# DM3390_CAM_FFC_MIPI_2LANE.net
KiCad netlist of a schematic drawn in Altium Designer
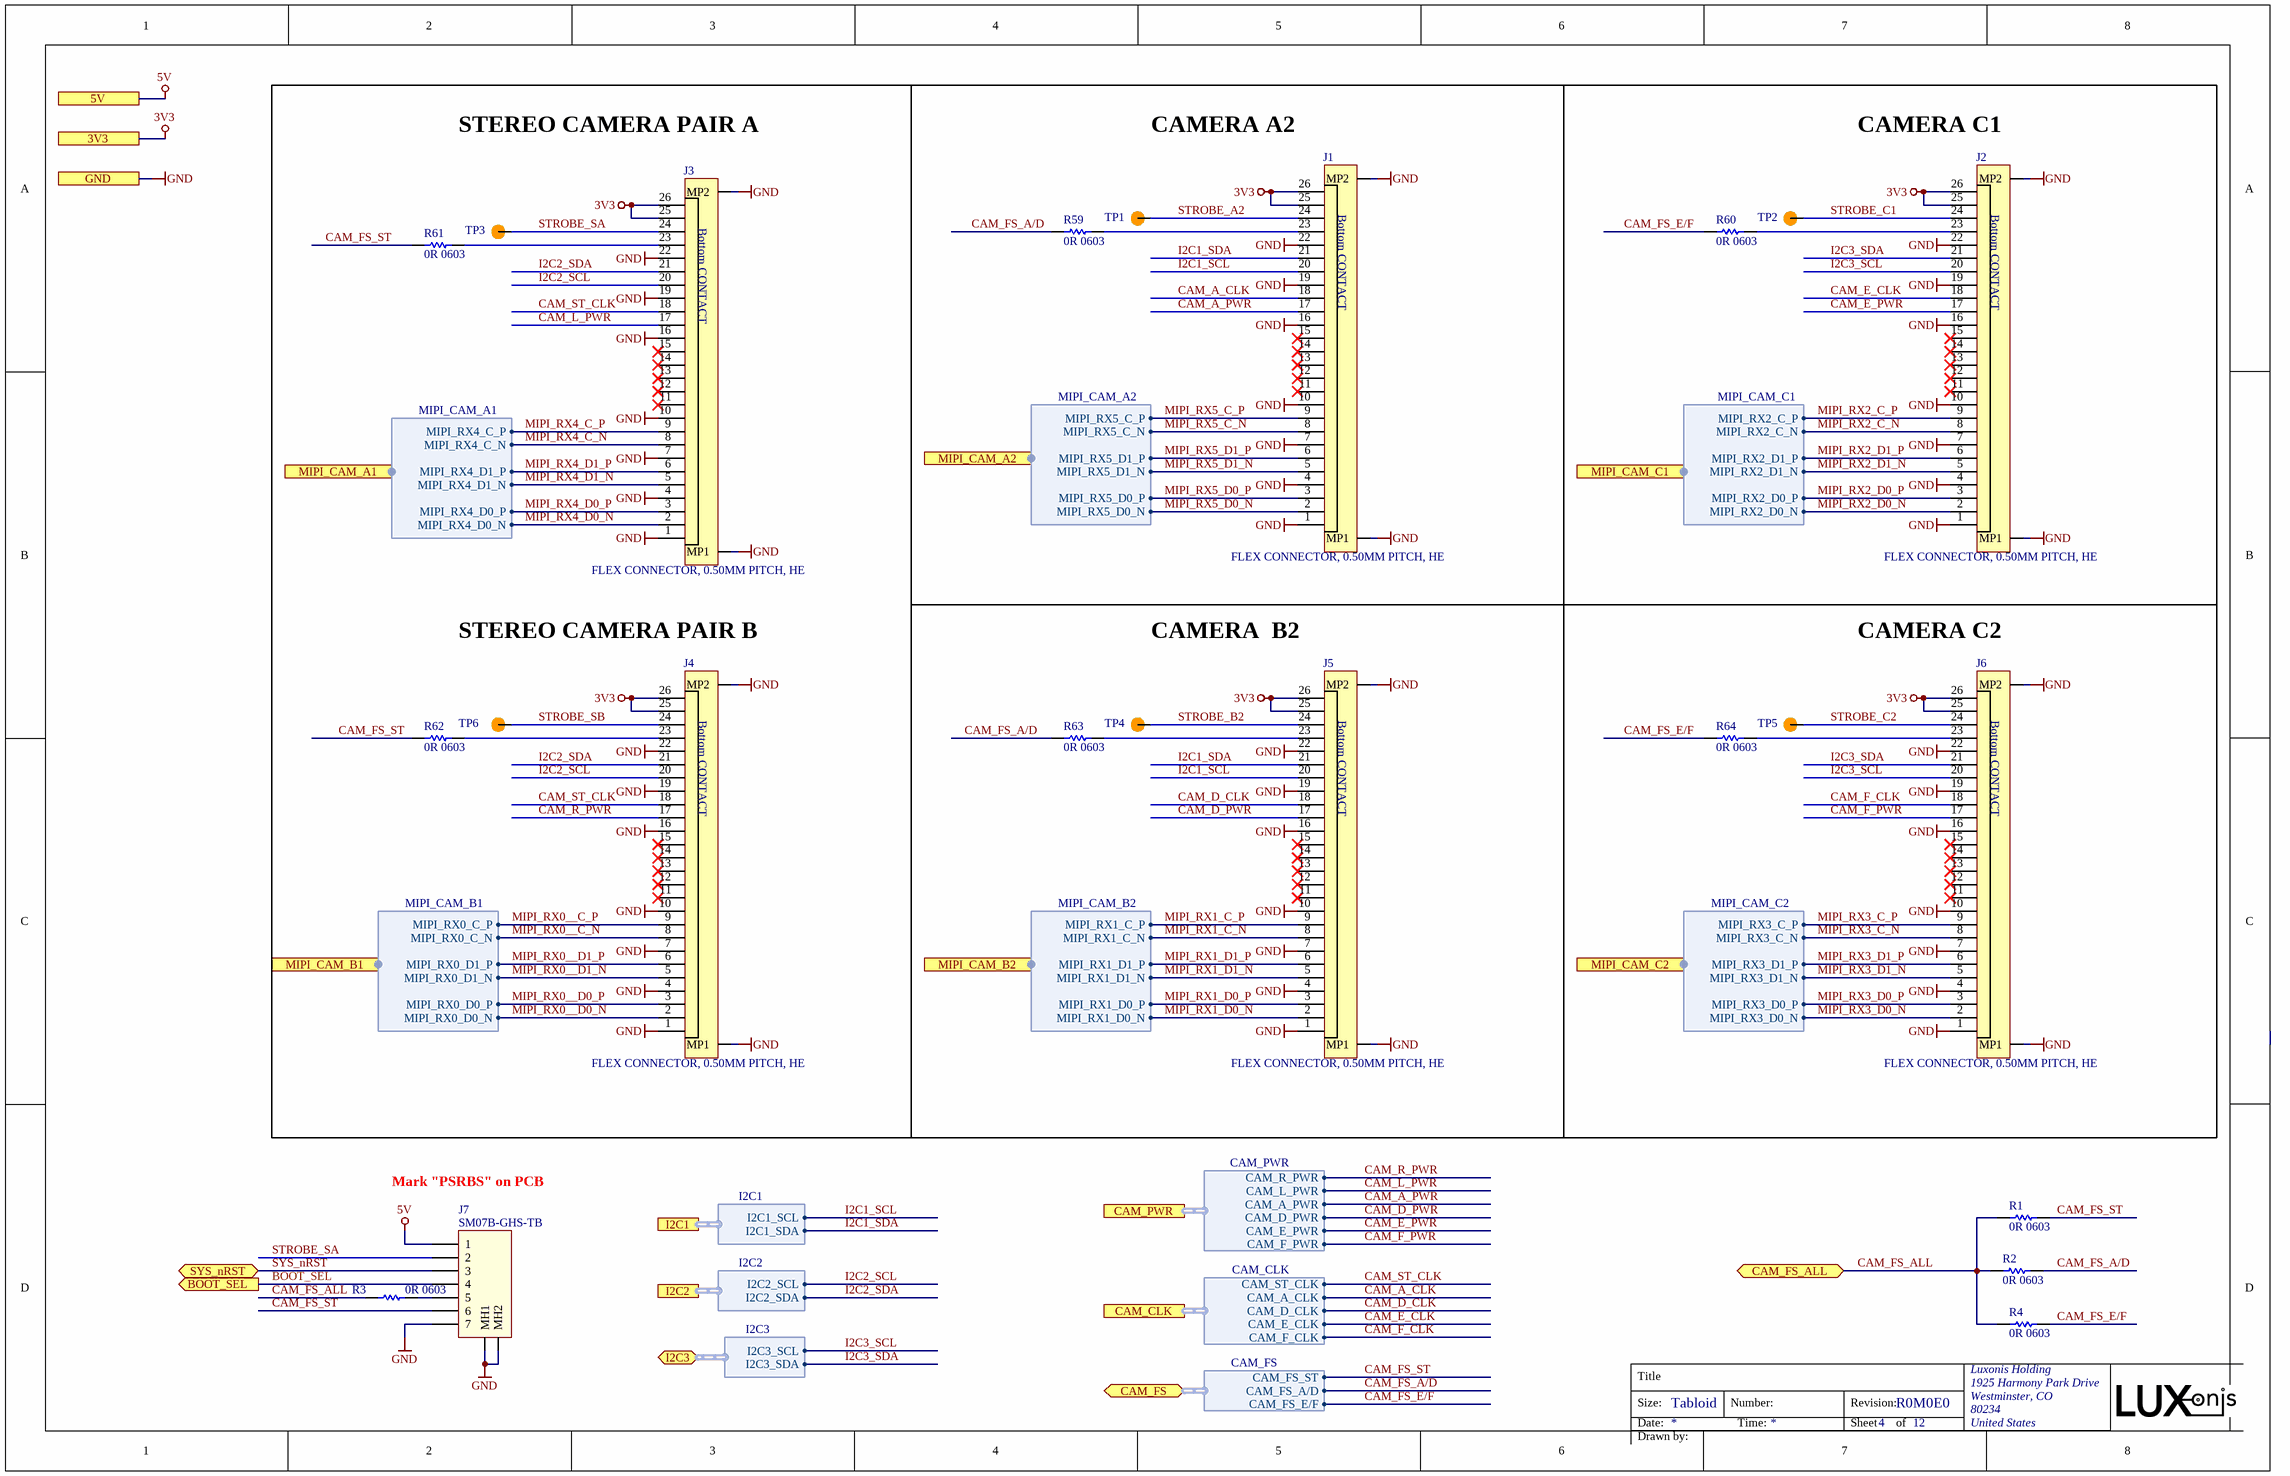
[diagram p0: DM3390_CAM_FFC_MIPI_2LANE.SchDoc]

(export (version "E")
  (design (tool "Eeschema 10.0.6"))
  (components
    (comp (ref "J1")
      (value "FLEX CONNECTOR, 0.50MM PITCH, HE")
      (footprint "F32R-1A7H1-11026")
      (description "26 Position FFC, FPC Connector Contacts, Bottom 0.020\" (0.50mm) Surface Mount, Right Angle")
      (libsource (lib "LuxonisMaster") (part "F32R-1A7H1-11026"))
    )
    (comp (ref "J2")
      (value "FLEX CONNECTOR, 0.50MM PITCH, HE")
      (footprint "F32R-1A7H1-11026")
      (description "26 Position FFC, FPC Connector Contacts, Bottom 0.020\" (0.50mm) Surface Mount, Right Angle")
      (libsource (lib "LuxonisMaster") (part "F32R-1A7H1-11026"))
    )
    (comp (ref "J3")
      (value "FLEX CONNECTOR, 0.50MM PITCH, HE")
      (footprint "F32R-1A7H1-11026")
      (description "26 Position FFC, FPC Connector Contacts, Bottom 0.020\" (0.50mm) Surface Mount, Right Angle")
      (libsource (lib "LuxonisMaster") (part "F32R-1A7H1-11026"))
    )
    (comp (ref "J4")
      (value "FLEX CONNECTOR, 0.50MM PITCH, HE")
      (footprint "F32R-1A7H1-11026")
      (description "26 Position FFC, FPC Connector Contacts, Bottom 0.020\" (0.50mm) Surface Mount, Right Angle")
      (libsource (lib "LuxonisMaster") (part "F32R-1A7H1-11026"))
    )
    (comp (ref "J5")
      (value "FLEX CONNECTOR, 0.50MM PITCH, HE")
      (footprint "F32R-1A7H1-11026")
      (description "26 Position FFC, FPC Connector Contacts, Bottom 0.020\" (0.50mm) Surface Mount, Right Angle")
      (libsource (lib "LuxonisMaster") (part "F32R-1A7H1-11026"))
    )
    (comp (ref "J6")
      (value "FLEX CONNECTOR, 0.50MM PITCH, HE")
      (footprint "F32R-1A7H1-11026")
      (description "26 Position FFC, FPC Connector Contacts, Bottom 0.020\" (0.50mm) Surface Mount, Right Angle")
      (libsource (lib "LuxonisMaster") (part "F32R-1A7H1-11026"))
    )
    (comp (ref "J7")
      (value "SM07B-GHS-TB")
      (footprint "SM07B-GHS-TB")
      (description "Conn Shrouded Header HDR 7 POS 1.25mm Solder RA Side Entry SMD T/R")
      (libsource (lib "LuxonisMaster") (part "SM07B-GHS-TB(LF)(SN)"))
    )
    (comp (ref "R1")
      (value "0R 0603")
      (footprint "RES_Altium_Vault_Generic:RESC0603(1608)_N")
      (fields (field (name "TOLERANCE") "5%"))
      (libsource (lib "LuxonisMaster") (part "CRCW06030000Z0EA"))
    )
    (comp (ref "R2")
      (value "0R 0603")
      (footprint "RES_Altium_Vault_Generic:RESC0603(1608)_N")
      (fields (field (name "TOLERANCE") "5%"))
      (libsource (lib "LuxonisMaster") (part "CRCW06030000Z0EA"))
    )
    (comp (ref "R3")
      (value "0R 0603")
      (footprint "RESC0603(1608)_N")
      (fields (field (name "TOLERANCE") "5%"))
      (libsource (lib "LuxonisMaster") (part "CRCW06030000Z0EA"))
    )
    (comp (ref "R4")
      (value "0R 0603")
      (footprint "RES_Altium_Vault_Generic:RESC0603(1608)_N")
      (fields (field (name "TOLERANCE") "5%"))
      (libsource (lib "LuxonisMaster") (part "CRCW06030000Z0EA"))
    )
    (comp (ref "R59")
      (value "0R 0603")
      (footprint "RES_Altium_Vault_Generic:RESC0603(1608)_N")
      (fields (field (name "TOLERANCE") "5%"))
      (libsource (lib "LuxonisMaster") (part "CRCW06030000Z0EA"))
    )
    (comp (ref "R60")
      (value "0R 0603")
      (footprint "RES_Altium_Vault_Generic:RESC0603(1608)_N")
      (fields (field (name "TOLERANCE") "5%"))
      (libsource (lib "LuxonisMaster") (part "CRCW06030000Z0EA"))
    )
    (comp (ref "R61")
      (value "0R 0603")
      (footprint "RES_Altium_Vault_Generic:RESC0603(1608)_N")
      (fields (field (name "TOLERANCE") "5%"))
      (libsource (lib "LuxonisMaster") (part "CRCW06030000Z0EA"))
    )
    (comp (ref "R62")
      (value "0R 0603")
      (footprint "RES_Altium_Vault_Generic:RESC0603(1608)_N")
      (fields (field (name "TOLERANCE") "5%"))
      (libsource (lib "LuxonisMaster") (part "CRCW06030000Z0EA"))
    )
    (comp (ref "R63")
      (value "0R 0603")
      (footprint "RES_Altium_Vault_Generic:RESC0603(1608)_N")
      (fields (field (name "TOLERANCE") "5%"))
      (libsource (lib "LuxonisMaster") (part "CRCW06030000Z0EA"))
    )
    (comp (ref "R64")
      (value "0R 0603")
      (footprint "RES_Altium_Vault_Generic:RESC0603(1608)_N")
      (fields (field (name "TOLERANCE") "5%"))
      (libsource (lib "LuxonisMaster") (part "CRCW06030000Z0EA"))
    )
    (comp (ref "TP1")
      (value "TP100_200_NS")
      (footprint "LuxonisMaster:TP100_200_NS")
      (libsource (lib "LuxonisMaster") (part "TEST_POINT"))
    )
    (comp (ref "TP2")
      (value "TP100_200_NS")
      (footprint "LuxonisMaster:TP100_200_NS")
      (libsource (lib "LuxonisMaster") (part "TEST_POINT"))
    )
    (comp (ref "TP3")
      (value "TP100_200_NS")
      (footprint "LuxonisMaster:TP100_200_NS")
      (libsource (lib "LuxonisMaster") (part "TEST_POINT"))
    )
    (comp (ref "TP4")
      (value "TP100_200_NS")
      (footprint "LuxonisMaster:TP100_200_NS")
      (libsource (lib "LuxonisMaster") (part "TEST_POINT"))
    )
    (comp (ref "TP5")
      (value "TP100_200_NS")
      (footprint "LuxonisMaster:TP100_200_NS")
      (libsource (lib "LuxonisMaster") (part "TEST_POINT"))
    )
    (comp (ref "TP6")
      (value "TP100_200_NS")
      (footprint "LuxonisMaster:TP100_200_NS")
      (libsource (lib "LuxonisMaster") (part "TEST_POINT"))
    )
  )
  (nets
    (net (code "13") (name "/BOOT_SEL") (class "Default")
      (node (ref "J7") (pin "4") (pinfunction "4_4") (pintype "passive"))
    )
    (net (code "14") (name "/CAM_A_CLK") (class "Default")
      (node (ref "J1") (pin "18") (pinfunction "18_18") (pintype "passive"))
    )
    (net (code "15") (name "/CAM_A_PWR") (class "Default")
      (node (ref "J1") (pin "17") (pinfunction "17_17") (pintype "passive"))
    )
    (net (code "16") (name "/CAM_D_CLK") (class "Default")
      (node (ref "J5") (pin "18") (pinfunction "18_18") (pintype "passive"))
    )
    (net (code "17") (name "/CAM_D_PWR") (class "Default")
      (node (ref "J5") (pin "17") (pinfunction "17_17") (pintype "passive"))
    )
    (net (code "18") (name "/CAM_E_CLK") (class "Default")
      (node (ref "J2") (pin "18") (pinfunction "18_18") (pintype "passive"))
    )
    (net (code "19") (name "/CAM_E_PWR") (class "Default")
      (node (ref "J2") (pin "17") (pinfunction "17_17") (pintype "passive"))
    )
    (net (code "20") (name "/CAM_FS_ALL") (class "Default")
      (node (ref "R1") (pin "1") (pinfunction "1_1") (pintype "passive"))
      (node (ref "R2") (pin "1") (pinfunction "1_1") (pintype "passive"))
      (node (ref "R3") (pin "1") (pinfunction "1_1") (pintype "passive"))
      (node (ref "R4") (pin "1") (pinfunction "1_1") (pintype "passive"))
    )
    (net (code "21") (name "/CAM_FS_A{slash}D") (class "Default")
      (node (ref "R2") (pin "2") (pinfunction "2_2") (pintype "passive"))
      (node (ref "R59") (pin "1") (pinfunction "1_1") (pintype "passive"))
      (node (ref "R63") (pin "1") (pinfunction "1_1") (pintype "passive"))
    )
    (net (code "22") (name "/CAM_FS_E{slash}F") (class "Default")
      (node (ref "R4") (pin "2") (pinfunction "2_2") (pintype "passive"))
      (node (ref "R60") (pin "1") (pinfunction "1_1") (pintype "passive"))
      (node (ref "R64") (pin "1") (pinfunction "1_1") (pintype "passive"))
    )
    (net (code "23") (name "/CAM_FS_ST") (class "Default")
      (node (ref "J7") (pin "6") (pinfunction "6_6") (pintype "passive"))
      (node (ref "R1") (pin "2") (pinfunction "2_2") (pintype "passive"))
      (node (ref "R61") (pin "1") (pinfunction "1_1") (pintype "passive"))
      (node (ref "R62") (pin "1") (pinfunction "1_1") (pintype "passive"))
    )
    (net (code "24") (name "/CAM_F_CLK") (class "Default")
      (node (ref "J6") (pin "18") (pinfunction "18_18") (pintype "passive"))
    )
    (net (code "25") (name "/CAM_F_PWR") (class "Default")
      (node (ref "J6") (pin "17") (pinfunction "17_17") (pintype "passive"))
    )
    (net (code "26") (name "/CAM_L_PWR") (class "Default")
      (node (ref "J3") (pin "17") (pinfunction "17_17") (pintype "passive"))
    )
    (net (code "27") (name "/CAM_R_PWR") (class "Default")
      (node (ref "J4") (pin "17") (pinfunction "17_17") (pintype "passive"))
    )
    (net (code "28") (name "/CAM_ST_CLK") (class "Default")
      (node (ref "J3") (pin "18") (pinfunction "18_18") (pintype "passive"))
      (node (ref "J4") (pin "18") (pinfunction "18_18") (pintype "passive"))
    )
    (net (code "29") (name "/I2C1_SCL") (class "Default")
      (node (ref "J1") (pin "20") (pinfunction "20_20") (pintype "passive"))
      (node (ref "J5") (pin "20") (pinfunction "20_20") (pintype "passive"))
    )
    (net (code "30") (name "/I2C1_SDA") (class "Default")
      (node (ref "J1") (pin "21") (pinfunction "21_21") (pintype "passive"))
      (node (ref "J5") (pin "21") (pinfunction "21_21") (pintype "passive"))
    )
    (net (code "31") (name "/I2C2_SCL") (class "Default")
      (node (ref "J3") (pin "20") (pinfunction "20_20") (pintype "passive"))
      (node (ref "J4") (pin "20") (pinfunction "20_20") (pintype "passive"))
    )
    (net (code "32") (name "/I2C2_SDA") (class "Default")
      (node (ref "J3") (pin "21") (pinfunction "21_21") (pintype "passive"))
      (node (ref "J4") (pin "21") (pinfunction "21_21") (pintype "passive"))
    )
    (net (code "33") (name "/I2C3_SCL") (class "Default")
      (node (ref "J2") (pin "20") (pinfunction "20_20") (pintype "passive"))
      (node (ref "J6") (pin "20") (pinfunction "20_20") (pintype "passive"))
    )
    (net (code "34") (name "/I2C3_SDA") (class "Default")
      (node (ref "J2") (pin "21") (pinfunction "21_21") (pintype "passive"))
      (node (ref "J6") (pin "21") (pinfunction "21_21") (pintype "passive"))
    )
    (net (code "35") (name "/MIPI_RX0__C_N") (class "Default")
      (node (ref "J4") (pin "8") (pinfunction "8_8") (pintype "passive"))
    )
    (net (code "36") (name "/MIPI_RX0__C_P") (class "Default")
      (node (ref "J4") (pin "9") (pinfunction "9_9") (pintype "passive"))
    )
    (net (code "37") (name "/MIPI_RX0__D0_N") (class "Default")
      (node (ref "J4") (pin "2") (pinfunction "2_2") (pintype "passive"))
    )
    (net (code "38") (name "/MIPI_RX0__D0_P") (class "Default")
      (node (ref "J4") (pin "3") (pinfunction "3_3") (pintype "passive"))
    )
    (net (code "39") (name "/MIPI_RX0__D1_N") (class "Default")
      (node (ref "J4") (pin "5") (pinfunction "5_5") (pintype "passive"))
    )
    (net (code "40") (name "/MIPI_RX0__D1_P") (class "Default")
      (node (ref "J4") (pin "6") (pinfunction "6_6") (pintype "passive"))
    )
    (net (code "41") (name "/MIPI_RX1_C_N") (class "Default")
      (node (ref "J5") (pin "8") (pinfunction "8_8") (pintype "passive"))
    )
    (net (code "42") (name "/MIPI_RX1_C_P") (class "Default")
      (node (ref "J5") (pin "9") (pinfunction "9_9") (pintype "passive"))
    )
    (net (code "43") (name "/MIPI_RX1_D0_N") (class "Default")
      (node (ref "J5") (pin "2") (pinfunction "2_2") (pintype "passive"))
    )
    (net (code "44") (name "/MIPI_RX1_D0_P") (class "Default")
      (node (ref "J5") (pin "3") (pinfunction "3_3") (pintype "passive"))
    )
    (net (code "45") (name "/MIPI_RX1_D1_N") (class "Default")
      (node (ref "J5") (pin "5") (pinfunction "5_5") (pintype "passive"))
    )
    (net (code "46") (name "/MIPI_RX1_D1_P") (class "Default")
      (node (ref "J5") (pin "6") (pinfunction "6_6") (pintype "passive"))
    )
    (net (code "47") (name "/MIPI_RX2_C_N") (class "Default")
      (node (ref "J2") (pin "8") (pinfunction "8_8") (pintype "passive"))
    )
    (net (code "48") (name "/MIPI_RX2_C_P") (class "Default")
      (node (ref "J2") (pin "9") (pinfunction "9_9") (pintype "passive"))
    )
    (net (code "49") (name "/MIPI_RX2_D0_N") (class "Default")
      (node (ref "J2") (pin "2") (pinfunction "2_2") (pintype "passive"))
    )
    (net (code "50") (name "/MIPI_RX2_D0_P") (class "Default")
      (node (ref "J2") (pin "3") (pinfunction "3_3") (pintype "passive"))
    )
    (net (code "51") (name "/MIPI_RX2_D1_N") (class "Default")
      (node (ref "J2") (pin "5") (pinfunction "5_5") (pintype "passive"))
    )
    (net (code "52") (name "/MIPI_RX2_D1_P") (class "Default")
      (node (ref "J2") (pin "6") (pinfunction "6_6") (pintype "passive"))
    )
    (net (code "53") (name "/MIPI_RX3_C_N") (class "Default")
      (node (ref "J6") (pin "8") (pinfunction "8_8") (pintype "passive"))
    )
    (net (code "54") (name "/MIPI_RX3_C_P") (class "Default")
      (node (ref "J6") (pin "9") (pinfunction "9_9") (pintype "passive"))
    )
    (net (code "55") (name "/MIPI_RX3_D0_N") (class "Default")
      (node (ref "J6") (pin "2") (pinfunction "2_2") (pintype "passive"))
    )
    (net (code "56") (name "/MIPI_RX3_D0_P") (class "Default")
      (node (ref "J6") (pin "3") (pinfunction "3_3") (pintype "passive"))
    )
    (net (code "57") (name "/MIPI_RX3_D1_N") (class "Default")
      (node (ref "J6") (pin "5") (pinfunction "5_5") (pintype "passive"))
    )
    (net (code "58") (name "/MIPI_RX3_D1_P") (class "Default")
      (node (ref "J6") (pin "6") (pinfunction "6_6") (pintype "passive"))
    )
    (net (code "59") (name "/MIPI_RX4_C_N") (class "Default")
      (node (ref "J3") (pin "8") (pinfunction "8_8") (pintype "passive"))
    )
    (net (code "60") (name "/MIPI_RX4_C_P") (class "Default")
      (node (ref "J3") (pin "9") (pinfunction "9_9") (pintype "passive"))
    )
    (net (code "61") (name "/MIPI_RX4_D0_N") (class "Default")
      (node (ref "J3") (pin "2") (pinfunction "2_2") (pintype "passive"))
    )
    (net (code "62") (name "/MIPI_RX4_D0_P") (class "Default")
      (node (ref "J3") (pin "3") (pinfunction "3_3") (pintype "passive"))
    )
    (net (code "63") (name "/MIPI_RX4_D1_N") (class "Default")
      (node (ref "J3") (pin "5") (pinfunction "5_5") (pintype "passive"))
    )
    (net (code "64") (name "/MIPI_RX4_D1_P") (class "Default")
      (node (ref "J3") (pin "6") (pinfunction "6_6") (pintype "passive"))
    )
    (net (code "65") (name "/MIPI_RX5_C_N") (class "Default")
      (node (ref "J1") (pin "8") (pinfunction "8_8") (pintype "passive"))
    )
    (net (code "66") (name "/MIPI_RX5_C_P") (class "Default")
      (node (ref "J1") (pin "9") (pinfunction "9_9") (pintype "passive"))
    )
    (net (code "67") (name "/MIPI_RX5_D0_N") (class "Default")
      (node (ref "J1") (pin "2") (pinfunction "2_2") (pintype "passive"))
    )
    (net (code "68") (name "/MIPI_RX5_D0_P") (class "Default")
      (node (ref "J1") (pin "3") (pinfunction "3_3") (pintype "passive"))
    )
    (net (code "69") (name "/MIPI_RX5_D1_N") (class "Default")
      (node (ref "J1") (pin "5") (pinfunction "5_5") (pintype "passive"))
    )
    (net (code "70") (name "/MIPI_RX5_D1_P") (class "Default")
      (node (ref "J1") (pin "6") (pinfunction "6_6") (pintype "passive"))
    )
    (net (code "71") (name "/STROBE_A2") (class "Default")
      (node (ref "J1") (pin "24") (pinfunction "24_24") (pintype "passive"))
      (node (ref "TP1") (pin "1") (pintype "passive"))
    )
    (net (code "72") (name "/STROBE_B2") (class "Default")
      (node (ref "J5") (pin "24") (pinfunction "24_24") (pintype "passive"))
      (node (ref "TP4") (pin "1") (pintype "passive"))
    )
    (net (code "73") (name "/STROBE_C1") (class "Default")
      (node (ref "J2") (pin "24") (pinfunction "24_24") (pintype "passive"))
      (node (ref "TP2") (pin "1") (pintype "passive"))
    )
    (net (code "74") (name "/STROBE_C2") (class "Default")
      (node (ref "J6") (pin "24") (pinfunction "24_24") (pintype "passive"))
      (node (ref "TP5") (pin "1") (pintype "passive"))
    )
    (net (code "75") (name "/STROBE_SA") (class "Default")
      (node (ref "J3") (pin "24") (pinfunction "24_24") (pintype "passive"))
      (node (ref "J7") (pin "2") (pinfunction "2_2") (pintype "passive"))
      (node (ref "TP3") (pin "1") (pintype "passive"))
    )
    (net (code "76") (name "/STROBE_SB") (class "Default")
      (node (ref "J4") (pin "24") (pinfunction "24_24") (pintype "passive"))
      (node (ref "TP6") (pin "1") (pintype "passive"))
    )
    (net (code "77") (name "/SYS_nRST") (class "Default")
      (node (ref "J7") (pin "3") (pinfunction "3_3") (pintype "passive"))
    )
    (net (code "90") (name "3V3") (class "Default")
      (node (ref "J1") (pin "25") (pinfunction "25_25") (pintype "passive"))
      (node (ref "J1") (pin "26") (pinfunction "26_26") (pintype "passive"))
      (node (ref "J2") (pin "25") (pinfunction "25_25") (pintype "passive"))
      (node (ref "J2") (pin "26") (pinfunction "26_26") (pintype "passive"))
      (node (ref "J3") (pin "25") (pinfunction "25_25") (pintype "passive"))
      (node (ref "J3") (pin "26") (pinfunction "26_26") (pintype "passive"))
      (node (ref "J4") (pin "25") (pinfunction "25_25") (pintype "passive"))
      (node (ref "J4") (pin "26") (pinfunction "26_26") (pintype "passive"))
      (node (ref "J5") (pin "25") (pinfunction "25_25") (pintype "passive"))
      (node (ref "J5") (pin "26") (pinfunction "26_26") (pintype "passive"))
      (node (ref "J6") (pin "25") (pinfunction "25_25") (pintype "passive"))
      (node (ref "J6") (pin "26") (pinfunction "26_26") (pintype "passive"))
    )
    (net (code "91") (name "5V") (class "Default")
      (node (ref "J7") (pin "1") (pinfunction "1_1") (pintype "passive"))
    )
    (net (code "92") (name "GND") (class "Default")
      (node (ref "J1") (pin "1") (pinfunction "1_1") (pintype "passive"))
      (node (ref "J1") (pin "10") (pinfunction "10_10") (pintype "passive"))
      (node (ref "J1") (pin "16") (pinfunction "16_16") (pintype "passive"))
      (node (ref "J1") (pin "19") (pinfunction "19_19") (pintype "passive"))
      (node (ref "J1") (pin "22") (pinfunction "22_22") (pintype "passive"))
      (node (ref "J1") (pin "4") (pinfunction "4_4") (pintype "passive"))
      (node (ref "J1") (pin "7") (pinfunction "7_7") (pintype "passive"))
      (node (ref "J1") (pin "MP1") (pinfunction "MP1_MP1") (pintype "passive"))
      (node (ref "J1") (pin "MP2") (pinfunction "MP2_MP2") (pintype "passive"))
      (node (ref "J2") (pin "1") (pinfunction "1_1") (pintype "passive"))
      (node (ref "J2") (pin "10") (pinfunction "10_10") (pintype "passive"))
      (node (ref "J2") (pin "16") (pinfunction "16_16") (pintype "passive"))
      (node (ref "J2") (pin "19") (pinfunction "19_19") (pintype "passive"))
      (node (ref "J2") (pin "22") (pinfunction "22_22") (pintype "passive"))
      (node (ref "J2") (pin "4") (pinfunction "4_4") (pintype "passive"))
      (node (ref "J2") (pin "7") (pinfunction "7_7") (pintype "passive"))
      (node (ref "J2") (pin "MP1") (pinfunction "MP1_MP1") (pintype "passive"))
      (node (ref "J2") (pin "MP2") (pinfunction "MP2_MP2") (pintype "passive"))
      (node (ref "J3") (pin "1") (pinfunction "1_1") (pintype "passive"))
      (node (ref "J3") (pin "10") (pinfunction "10_10") (pintype "passive"))
      (node (ref "J3") (pin "16") (pinfunction "16_16") (pintype "passive"))
      (node (ref "J3") (pin "19") (pinfunction "19_19") (pintype "passive"))
      (node (ref "J3") (pin "22") (pinfunction "22_22") (pintype "passive"))
      (node (ref "J3") (pin "4") (pinfunction "4_4") (pintype "passive"))
      (node (ref "J3") (pin "7") (pinfunction "7_7") (pintype "passive"))
      (node (ref "J3") (pin "MP1") (pinfunction "MP1_MP1") (pintype "passive"))
      (node (ref "J3") (pin "MP2") (pinfunction "MP2_MP2") (pintype "passive"))
      (node (ref "J4") (pin "1") (pinfunction "1_1") (pintype "passive"))
      (node (ref "J4") (pin "10") (pinfunction "10_10") (pintype "passive"))
      (node (ref "J4") (pin "16") (pinfunction "16_16") (pintype "passive"))
      (node (ref "J4") (pin "19") (pinfunction "19_19") (pintype "passive"))
      (node (ref "J4") (pin "22") (pinfunction "22_22") (pintype "passive"))
      (node (ref "J4") (pin "4") (pinfunction "4_4") (pintype "passive"))
      (node (ref "J4") (pin "7") (pinfunction "7_7") (pintype "passive"))
      (node (ref "J4") (pin "MP1") (pinfunction "MP1_MP1") (pintype "passive"))
      (node (ref "J4") (pin "MP2") (pinfunction "MP2_MP2") (pintype "passive"))
      (node (ref "J5") (pin "1") (pinfunction "1_1") (pintype "passive"))
      (node (ref "J5") (pin "10") (pinfunction "10_10") (pintype "passive"))
      (node (ref "J5") (pin "16") (pinfunction "16_16") (pintype "passive"))
      (node (ref "J5") (pin "19") (pinfunction "19_19") (pintype "passive"))
      (node (ref "J5") (pin "22") (pinfunction "22_22") (pintype "passive"))
      (node (ref "J5") (pin "4") (pinfunction "4_4") (pintype "passive"))
      (node (ref "J5") (pin "7") (pinfunction "7_7") (pintype "passive"))
      (node (ref "J5") (pin "MP1") (pinfunction "MP1_MP1") (pintype "passive"))
      (node (ref "J5") (pin "MP2") (pinfunction "MP2_MP2") (pintype "passive"))
      (node (ref "J6") (pin "1") (pinfunction "1_1") (pintype "passive"))
      (node (ref "J6") (pin "10") (pinfunction "10_10") (pintype "passive"))
      (node (ref "J6") (pin "16") (pinfunction "16_16") (pintype "passive"))
      (node (ref "J6") (pin "19") (pinfunction "19_19") (pintype "passive"))
      (node (ref "J6") (pin "22") (pinfunction "22_22") (pintype "passive"))
      (node (ref "J6") (pin "4") (pinfunction "4_4") (pintype "passive"))
      (node (ref "J6") (pin "7") (pinfunction "7_7") (pintype "passive"))
      (node (ref "J6") (pin "MP1") (pinfunction "MP1_MP1") (pintype "passive"))
      (node (ref "J6") (pin "MP2") (pinfunction "MP2_MP2") (pintype "passive"))
      (node (ref "J7") (pin "7") (pinfunction "7_7") (pintype "passive"))
      (node (ref "J7") (pin "MH1") (pinfunction "MH1_MH1") (pintype "passive"))
      (node (ref "J7") (pin "MH2") (pinfunction "MH2_MH2") (pintype "passive"))
    )
    (net (code "93") (name "Net-(J1-Pad23)") (class "Default")
      (node (ref "J1") (pin "23") (pinfunction "23_23") (pintype "passive"))
      (node (ref "R59") (pin "2") (pinfunction "2_2") (pintype "passive"))
    )
    (net (code "94") (name "Net-(J2-Pad23)") (class "Default")
      (node (ref "J2") (pin "23") (pinfunction "23_23") (pintype "passive"))
      (node (ref "R60") (pin "2") (pinfunction "2_2") (pintype "passive"))
    )
    (net (code "95") (name "Net-(J3-Pad23)") (class "Default")
      (node (ref "J3") (pin "23") (pinfunction "23_23") (pintype "passive"))
      (node (ref "R61") (pin "2") (pinfunction "2_2") (pintype "passive"))
    )
    (net (code "96") (name "Net-(J4-Pad23)") (class "Default")
      (node (ref "J4") (pin "23") (pinfunction "23_23") (pintype "passive"))
      (node (ref "R62") (pin "2") (pinfunction "2_2") (pintype "passive"))
    )
    (net (code "97") (name "Net-(J5-Pad23)") (class "Default")
      (node (ref "J5") (pin "23") (pinfunction "23_23") (pintype "passive"))
      (node (ref "R63") (pin "2") (pinfunction "2_2") (pintype "passive"))
    )
    (net (code "98") (name "Net-(J6-Pad23)") (class "Default")
      (node (ref "J6") (pin "23") (pinfunction "23_23") (pintype "passive"))
      (node (ref "R64") (pin "2") (pinfunction "2_2") (pintype "passive"))
    )
    (net (code "99") (name "Net-(J7-Pad5)") (class "Default")
      (node (ref "J7") (pin "5") (pinfunction "5_5") (pintype "passive"))
      (node (ref "R3") (pin "2") (pinfunction "2_2") (pintype "passive"))
    )
    (net (code "100") (name "unconnected-(J1-Pad11)") (class "Default")
      (node (ref "J1") (pin "11") (pinfunction "11_11") (pintype "passive+no_connect"))
    )
    (net (code "101") (name "unconnected-(J1-Pad12)") (class "Default")
      (node (ref "J1") (pin "12") (pinfunction "12_12") (pintype "passive+no_connect"))
    )
    (net (code "102") (name "unconnected-(J1-Pad13)") (class "Default")
      (node (ref "J1") (pin "13") (pinfunction "13_13") (pintype "passive+no_connect"))
    )
    (net (code "103") (name "unconnected-(J1-Pad14)") (class "Default")
      (node (ref "J1") (pin "14") (pinfunction "14_14") (pintype "passive+no_connect"))
    )
    (net (code "104") (name "unconnected-(J1-Pad15)") (class "Default")
      (node (ref "J1") (pin "15") (pinfunction "15_15") (pintype "passive+no_connect"))
    )
    (net (code "105") (name "unconnected-(J2-Pad11)") (class "Default")
      (node (ref "J2") (pin "11") (pinfunction "11_11") (pintype "passive+no_connect"))
    )
    (net (code "106") (name "unconnected-(J2-Pad12)") (class "Default")
      (node (ref "J2") (pin "12") (pinfunction "12_12") (pintype "passive+no_connect"))
    )
    (net (code "107") (name "unconnected-(J2-Pad13)") (class "Default")
      (node (ref "J2") (pin "13") (pinfunction "13_13") (pintype "passive+no_connect"))
    )
    (net (code "108") (name "unconnected-(J2-Pad14)") (class "Default")
      (node (ref "J2") (pin "14") (pinfunction "14_14") (pintype "passive+no_connect"))
    )
    (net (code "109") (name "unconnected-(J2-Pad15)") (class "Default")
      (node (ref "J2") (pin "15") (pinfunction "15_15") (pintype "passive+no_connect"))
    )
    (net (code "110") (name "unconnected-(J3-Pad11)") (class "Default")
      (node (ref "J3") (pin "11") (pinfunction "11_11") (pintype "passive+no_connect"))
    )
    (net (code "111") (name "unconnected-(J3-Pad12)") (class "Default")
      (node (ref "J3") (pin "12") (pinfunction "12_12") (pintype "passive+no_connect"))
    )
    (net (code "112") (name "unconnected-(J3-Pad13)") (class "Default")
      (node (ref "J3") (pin "13") (pinfunction "13_13") (pintype "passive+no_connect"))
    )
    (net (code "113") (name "unconnected-(J3-Pad14)") (class "Default")
      (node (ref "J3") (pin "14") (pinfunction "14_14") (pintype "passive+no_connect"))
    )
    (net (code "114") (name "unconnected-(J3-Pad15)") (class "Default")
      (node (ref "J3") (pin "15") (pinfunction "15_15") (pintype "passive+no_connect"))
    )
    (net (code "115") (name "unconnected-(J4-Pad11)") (class "Default")
      (node (ref "J4") (pin "11") (pinfunction "11_11") (pintype "passive+no_connect"))
    )
    (net (code "116") (name "unconnected-(J4-Pad12)") (class "Default")
      (node (ref "J4") (pin "12") (pinfunction "12_12") (pintype "passive+no_connect"))
    )
    (net (code "117") (name "unconnected-(J4-Pad13)") (class "Default")
      (node (ref "J4") (pin "13") (pinfunction "13_13") (pintype "passive+no_connect"))
    )
    (net (code "118") (name "unconnected-(J4-Pad14)") (class "Default")
      (node (ref "J4") (pin "14") (pinfunction "14_14") (pintype "passive+no_connect"))
    )
    (net (code "119") (name "unconnected-(J4-Pad15)") (class "Default")
      (node (ref "J4") (pin "15") (pinfunction "15_15") (pintype "passive+no_connect"))
    )
    (net (code "120") (name "unconnected-(J5-Pad11)") (class "Default")
      (node (ref "J5") (pin "11") (pinfunction "11_11") (pintype "passive+no_connect"))
    )
    (net (code "121") (name "unconnected-(J5-Pad12)") (class "Default")
      (node (ref "J5") (pin "12") (pinfunction "12_12") (pintype "passive+no_connect"))
    )
    (net (code "122") (name "unconnected-(J5-Pad13)") (class "Default")
      (node (ref "J5") (pin "13") (pinfunction "13_13") (pintype "passive+no_connect"))
    )
    (net (code "123") (name "unconnected-(J5-Pad14)") (class "Default")
      (node (ref "J5") (pin "14") (pinfunction "14_14") (pintype "passive+no_connect"))
    )
    (net (code "124") (name "unconnected-(J5-Pad15)") (class "Default")
      (node (ref "J5") (pin "15") (pinfunction "15_15") (pintype "passive+no_connect"))
    )
    (net (code "125") (name "unconnected-(J6-Pad11)") (class "Default")
      (node (ref "J6") (pin "11") (pinfunction "11_11") (pintype "passive+no_connect"))
    )
    (net (code "126") (name "unconnected-(J6-Pad12)") (class "Default")
      (node (ref "J6") (pin "12") (pinfunction "12_12") (pintype "passive+no_connect"))
    )
    (net (code "127") (name "unconnected-(J6-Pad13)") (class "Default")
      (node (ref "J6") (pin "13") (pinfunction "13_13") (pintype "passive+no_connect"))
    )
    (net (code "128") (name "unconnected-(J6-Pad14)") (class "Default")
      (node (ref "J6") (pin "14") (pinfunction "14_14") (pintype "passive+no_connect"))
    )
    (net (code "129") (name "unconnected-(J6-Pad15)") (class "Default")
      (node (ref "J6") (pin "15") (pinfunction "15_15") (pintype "passive+no_connect"))
    )
  )
)
